# amp01.net
KiCad netlist of a schematic drawn in EAGLE
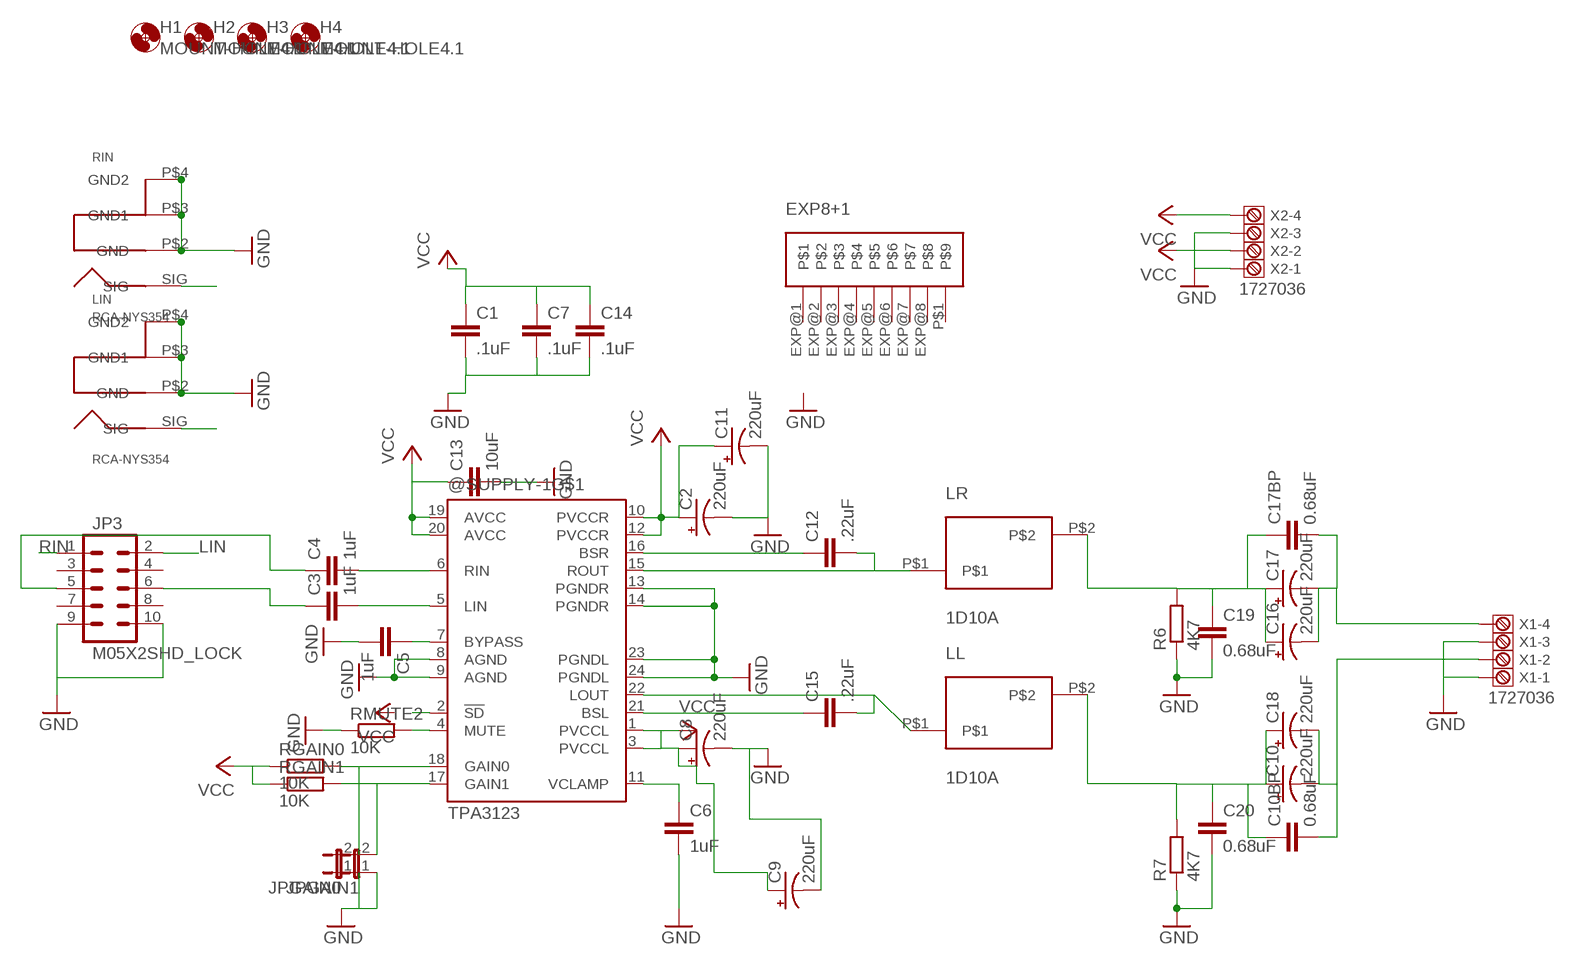
[diagram p0: schematic, sheet 1]

(export (version "E")
  (design (tool "Eeschema 10.0.6"))
  (components
    (comp (ref "@SUPPLY-1")
      (value "TPA3123")
      (footprint "eagle-import:PWP-TSSOP24")
      (libsource (lib "eagle-import") (part "TPA3123"))
    )
    (comp (ref "C1")
      (value ".1uF")
      (footprint "eagle-import:C0805")
      (libsource (lib "eagle-import") (part "C-EUC0805"))
    )
    (comp (ref "C2")
      (value "220uF")
      (footprint "eagle-import:PANASONIC_F")
      (libsource (lib "eagle-import") (part "CPOL-USF"))
    )
    (comp (ref "C3")
      (value "1uF")
      (footprint "eagle-import:C102_152-062X184")
      (libsource (lib "eagle-import") (part "C-EU102_152-062X184"))
    )
    (comp (ref "C4")
      (value "1uF")
      (footprint "eagle-import:C102_152-062X184")
      (libsource (lib "eagle-import") (part "C-EU102_152-062X184"))
    )
    (comp (ref "C5")
      (value "1uF")
      (footprint "eagle-import:C0805")
      (libsource (lib "eagle-import") (part "C-EUC0805"))
    )
    (comp (ref "C6")
      (value "1uF")
      (footprint "eagle-import:C0805")
      (libsource (lib "eagle-import") (part "C-EUC0805"))
    )
    (comp (ref "C7")
      (value ".1uF")
      (footprint "eagle-import:C0805")
      (libsource (lib "eagle-import") (part "C-EUC0805"))
    )
    (comp (ref "C8")
      (value "220uF")
      (footprint "eagle-import:PANASONIC_F")
      (libsource (lib "eagle-import") (part "CPOL-USF"))
    )
    (comp (ref "C9")
      (value "220uF")
      (footprint "eagle-import:PANASONIC_F")
      (libsource (lib "eagle-import") (part "CPOL-USF"))
    )
    (comp (ref "C10")
      (value "220uF")
      (footprint "eagle-import:PANASONIC_F")
      (libsource (lib "eagle-import") (part "CPOL-USF"))
    )
    (comp (ref "C10BP")
      (value "0.68uF")
      (footprint "eagle-import:C050-055X075")
      (libsource (lib "eagle-import") (part "C-EU050-055X075"))
    )
    (comp (ref "C11")
      (value "220uF")
      (footprint "eagle-import:PANASONIC_F")
      (libsource (lib "eagle-import") (part "CPOL-USF"))
    )
    (comp (ref "C12")
      (value ".22uF")
      (footprint "eagle-import:C0805")
      (libsource (lib "eagle-import") (part "C-EUC0805"))
    )
    (comp (ref "C13")
      (value "10uF")
      (footprint "eagle-import:C1210")
      (libsource (lib "eagle-import") (part "C-EUC1210"))
    )
    (comp (ref "C14")
      (value ".1uF")
      (footprint "eagle-import:C0805")
      (libsource (lib "eagle-import") (part "C-EUC0805"))
    )
    (comp (ref "C15")
      (value ".22uF")
      (footprint "eagle-import:C0805")
      (libsource (lib "eagle-import") (part "C-EUC0805"))
    )
    (comp (ref "C16")
      (value "220uF")
      (footprint "eagle-import:PANASONIC_F")
      (libsource (lib "eagle-import") (part "CPOL-USF"))
    )
    (comp (ref "C17")
      (value "220uF")
      (footprint "eagle-import:PANASONIC_F")
      (libsource (lib "eagle-import") (part "CPOL-USF"))
    )
    (comp (ref "C17BP")
      (value "0.68uF")
      (footprint "eagle-import:C050-055X075")
      (libsource (lib "eagle-import") (part "C-EU050-055X075"))
    )
    (comp (ref "C18")
      (value "220uF")
      (footprint "eagle-import:PANASONIC_F")
      (libsource (lib "eagle-import") (part "CPOL-USF"))
    )
    (comp (ref "C19")
      (value "0.68uF")
      (footprint "eagle-import:C050-055X075")
      (libsource (lib "eagle-import") (part "C-EU050-055X075"))
    )
    (comp (ref "C20")
      (value "0.68uF")
      (footprint "eagle-import:C050-055X075")
      (libsource (lib "eagle-import") (part "C-EU050-055X075"))
    )
    (comp (ref "H1")
      (value "MOUNT-HOLE4.1")
      (footprint "eagle-import:4,1")
      (libsource (lib "eagle-import") (part "MOUNT-HOLE4.1"))
    )
    (comp (ref "H2")
      (value "MOUNT-HOLE4.1")
      (footprint "eagle-import:4,1")
      (libsource (lib "eagle-import") (part "MOUNT-HOLE4.1"))
    )
    (comp (ref "H3")
      (value "MOUNT-HOLE4.1")
      (footprint "eagle-import:4,1")
      (libsource (lib "eagle-import") (part "MOUNT-HOLE4.1"))
    )
    (comp (ref "H4")
      (value "MOUNT-HOLE4.1")
      (footprint "eagle-import:4,1")
      (libsource (lib "eagle-import") (part "MOUNT-HOLE4.1"))
    )
    (comp (ref "JP3")
      (value "M05X2SHD_LOCK")
      (footprint "eagle-import:2X5-SHROUDED_LOCK")
      (libsource (lib "eagle-import") (part "M05X2SHD_LOCK"))
    )
    (comp (ref "JPGAIN0")
      (value "JUMPER-2PTH_LOCK")
      (footprint "eagle-import:1X02_LOCK")
      (libsource (lib "eagle-import") (part "JUMPER-2PTH_LOCK"))
    )
    (comp (ref "JPGAIN1")
      (value "JUMPER-2PTH_LOCK")
      (footprint "eagle-import:1X02_LOCK")
      (libsource (lib "eagle-import") (part "JUMPER-2PTH_LOCK"))
    )
    (comp (ref "LIN")
      (value "RCA-NYS354")
      (footprint "eagle-import:NYS354")
      (libsource (lib "eagle-import") (part "RCA-NYS354"))
    )
    (comp (ref "LL")
      (value "1D10A")
      (footprint "eagle-import:1D10APAC")
      (libsource (lib "eagle-import") (part "1D10A"))
    )
    (comp (ref "LR")
      (value "1D10A")
      (footprint "eagle-import:1D10APAC")
      (libsource (lib "eagle-import") (part "1D10A"))
    )
    (comp (ref "R6")
      (value "4K7")
      (footprint "eagle-import:R0805")
      (libsource (lib "eagle-import") (part "R-EU_R0805"))
    )
    (comp (ref "R7")
      (value "4K7")
      (footprint "eagle-import:R0805")
      (libsource (lib "eagle-import") (part "R-EU_R0805"))
    )
    (comp (ref "RGAIN0")
      (value "10K")
      (footprint "eagle-import:R0805")
      (libsource (lib "eagle-import") (part "R-EU_R0805"))
    )
    (comp (ref "RGAIN1")
      (value "10K")
      (footprint "eagle-import:R0805")
      (libsource (lib "eagle-import") (part "R-EU_R0805"))
    )
    (comp (ref "RIN")
      (value "RCA-NYS354")
      (footprint "eagle-import:NYS354")
      (libsource (lib "eagle-import") (part "RCA-NYS354"))
    )
    (comp (ref "RMUTE2")
      (value "10K")
      (footprint "eagle-import:R0805")
      (libsource (lib "eagle-import") (part "R-EU_R0805"))
    )
    (comp (ref "X1")
      (value "1727036")
      (footprint "eagle-import:1727036")
      (fields (field (name "MF") "FARNELL"))
      (libsource (lib "eagle-import") (part "1727036"))
    )
    (comp (ref "X2")
      (value "1727036")
      (footprint "eagle-import:1727036")
      (fields
        (field (name "MF") "FARNELL")
        (field (name "MF_1") "FARNELL")
        (field (name "MPN") "1727036")
        (field (name "OC_FARNELL") "3704592")
        (field (name "OC_NEWARK") "71C4114")
      )
      (libsource (lib "eagle-import") (part "1727036"))
    )
  )
  (nets
    (net (code "1") (name "/LIN") (class "Default")
      (node (ref "JP3") (pin "2") (pinfunction "2_2") (pintype "passive"))
      (node (ref "LIN") (pin "SIG") (pinfunction "SIG_SIG") (pintype "bidirectional"))
    )
    (net (code "2") (name "/RIN") (class "Default")
      (node (ref "JP3") (pin "1") (pinfunction "1_1") (pintype "passive"))
      (node (ref "RIN") (pin "SIG") (pinfunction "SIG_SIG") (pintype "bidirectional"))
    )
    (net (code "3") (name "GND") (class "Default")
      (node (ref "@SUPPLY-1") (pin "13") (pinfunction "PGNDR_13") (pintype "input"))
      (node (ref "@SUPPLY-1") (pin "14") (pinfunction "PGNDR_14") (pintype "input"))
      (node (ref "@SUPPLY-1") (pin "23") (pinfunction "PGNDL_23") (pintype "input"))
      (node (ref "@SUPPLY-1") (pin "24") (pinfunction "PGNDL_24") (pintype "input"))
      (node (ref "@SUPPLY-1") (pin "8") (pinfunction "AGND_8") (pintype "input"))
      (node (ref "@SUPPLY-1") (pin "9") (pinfunction "AGND_9") (pintype "input"))
      (node (ref "C1") (pin "2") (pinfunction "2_2") (pintype "passive"))
      (node (ref "C11") (pin "-") (pinfunction "-_-") (pintype "passive"))
      (node (ref "C13") (pin "2") (pinfunction "2_2") (pintype "passive"))
      (node (ref "C14") (pin "2") (pinfunction "2_2") (pintype "passive"))
      (node (ref "C19") (pin "2") (pinfunction "2_2") (pintype "passive"))
      (node (ref "C2") (pin "-") (pinfunction "-_-") (pintype "passive"))
      (node (ref "C20") (pin "2") (pinfunction "2_2") (pintype "passive"))
      (node (ref "C5") (pin "2") (pinfunction "2_2") (pintype "passive"))
      (node (ref "C6") (pin "2") (pinfunction "2_2") (pintype "passive"))
      (node (ref "C7") (pin "2") (pinfunction "2_2") (pintype "passive"))
      (node (ref "C8") (pin "-") (pinfunction "-_-") (pintype "passive"))
      (node (ref "C9") (pin "-") (pinfunction "-_-") (pintype "passive"))
      (node (ref "JP3") (pin "10") (pinfunction "10_10") (pintype "passive"))
      (node (ref "JP3") (pin "9") (pinfunction "9_9") (pintype "passive"))
      (node (ref "JPGAIN0") (pin "1") (pinfunction "1_1") (pintype "passive"))
      (node (ref "JPGAIN1") (pin "1") (pinfunction "1_1") (pintype "passive"))
      (node (ref "LIN") (pin "P$2") (pinfunction "GND_P$2") (pintype "bidirectional"))
      (node (ref "LIN") (pin "P$3") (pinfunction "GND1_P$3") (pintype "bidirectional"))
      (node (ref "LIN") (pin "P$4") (pinfunction "GND2_P$4") (pintype "bidirectional"))
      (node (ref "R6") (pin "1") (pinfunction "1_1") (pintype "passive"))
      (node (ref "R7") (pin "1") (pinfunction "1_1") (pintype "passive"))
      (node (ref "RIN") (pin "P$2") (pinfunction "GND_P$2") (pintype "bidirectional"))
      (node (ref "RIN") (pin "P$3") (pinfunction "GND1_P$3") (pintype "bidirectional"))
      (node (ref "RIN") (pin "P$4") (pinfunction "GND2_P$4") (pintype "bidirectional"))
      (node (ref "RMUTE2") (pin "1") (pinfunction "1_1") (pintype "passive"))
      (node (ref "X1") (pin "1") (pinfunction "1_1") (pintype "passive"))
      (node (ref "X1") (pin "3") (pinfunction "1_3") (pintype "passive"))
      (node (ref "X2") (pin "1") (pinfunction "1_1") (pintype "passive"))
      (node (ref "X2") (pin "3") (pinfunction "1_3") (pintype "passive"))
    )
    (net (code "4") (name "Net-(@SUPPLY-1A-BSL)") (class "Default")
      (node (ref "@SUPPLY-1") (pin "21") (pinfunction "BSL_21") (pintype "passive"))
      (node (ref "C15") (pin "1") (pinfunction "1_1") (pintype "passive"))
    )
    (net (code "5") (name "Net-(@SUPPLY-1A-BSR)") (class "Default")
      (node (ref "@SUPPLY-1") (pin "16") (pinfunction "BSR_16") (pintype "passive"))
      (node (ref "C12") (pin "1") (pinfunction "1_1") (pintype "passive"))
    )
    (net (code "6") (name "Net-(@SUPPLY-1A-BYPASS)") (class "Default")
      (node (ref "@SUPPLY-1") (pin "7") (pinfunction "BYPASS_7") (pintype "input"))
      (node (ref "C5") (pin "1") (pinfunction "1_1") (pintype "passive"))
    )
    (net (code "7") (name "Net-(@SUPPLY-1A-GAIN0)") (class "Default")
      (node (ref "@SUPPLY-1") (pin "18") (pinfunction "GAIN0_18") (pintype "input"))
      (node (ref "JPGAIN0") (pin "2") (pinfunction "2_2") (pintype "passive"))
      (node (ref "RGAIN0") (pin "2") (pinfunction "2_2") (pintype "passive"))
    )
    (net (code "8") (name "Net-(@SUPPLY-1A-GAIN1)") (class "Default")
      (node (ref "@SUPPLY-1") (pin "17") (pinfunction "GAIN1_17") (pintype "input"))
      (node (ref "JPGAIN1") (pin "2") (pinfunction "2_2") (pintype "passive"))
      (node (ref "RGAIN1") (pin "2") (pinfunction "2_2") (pintype "passive"))
    )
    (net (code "9") (name "Net-(@SUPPLY-1A-LIN)") (class "Default")
      (node (ref "@SUPPLY-1") (pin "5") (pinfunction "LIN_5") (pintype "input"))
      (node (ref "C3") (pin "2") (pinfunction "2_2") (pintype "passive"))
    )
    (net (code "10") (name "Net-(@SUPPLY-1A-LOUT)") (class "Default")
      (node (ref "@SUPPLY-1") (pin "22") (pinfunction "LOUT_22") (pintype "output"))
      (node (ref "C15") (pin "2") (pinfunction "2_2") (pintype "passive"))
      (node (ref "LL") (pin "P$1") (pinfunction "P$1_P$1") (pintype "bidirectional"))
    )
    (net (code "11") (name "Net-(@SUPPLY-1A-MUTE)") (class "Default")
      (node (ref "@SUPPLY-1") (pin "4") (pinfunction "MUTE_4") (pintype "input"))
      (node (ref "RMUTE2") (pin "2") (pinfunction "2_2") (pintype "passive"))
    )
    (net (code "12") (name "Net-(@SUPPLY-1A-RIN)") (class "Default")
      (node (ref "@SUPPLY-1") (pin "6") (pinfunction "RIN_6") (pintype "input"))
      (node (ref "C4") (pin "2") (pinfunction "2_2") (pintype "passive"))
    )
    (net (code "13") (name "Net-(@SUPPLY-1A-ROUT)") (class "Default")
      (node (ref "@SUPPLY-1") (pin "15") (pinfunction "ROUT_15") (pintype "output"))
      (node (ref "C12") (pin "2") (pinfunction "2_2") (pintype "passive"))
      (node (ref "LR") (pin "P$1") (pinfunction "P$1_P$1") (pintype "bidirectional"))
    )
    (net (code "14") (name "Net-(@SUPPLY-1A-VCLAMP)") (class "Default")
      (node (ref "@SUPPLY-1") (pin "11") (pinfunction "VCLAMP_11") (pintype "input"))
      (node (ref "C6") (pin "1") (pinfunction "1_1") (pintype "passive"))
    )
    (net (code "15") (name "Net-(C3-Pad1)") (class "Default")
      (node (ref "C3") (pin "1") (pinfunction "1_1") (pintype "passive"))
      (node (ref "JP3") (pin "6") (pinfunction "6_6") (pintype "passive"))
    )
    (net (code "16") (name "Net-(C4-Pad1)") (class "Default")
      (node (ref "C4") (pin "1") (pinfunction "1_1") (pintype "passive"))
      (node (ref "JP3") (pin "5") (pinfunction "5_5") (pintype "passive"))
    )
    (net (code "17") (name "Net-(C10-Pad+)") (class "Default")
      (node (ref "C10") (pin "+") (pinfunction "+_+") (pintype "passive"))
      (node (ref "C10BP") (pin "1") (pinfunction "1_1") (pintype "passive"))
      (node (ref "C18") (pin "+") (pinfunction "+_+") (pintype "passive"))
      (node (ref "C20") (pin "1") (pinfunction "1_1") (pintype "passive"))
      (node (ref "LL") (pin "P$2") (pinfunction "P$2_P$2") (pintype "bidirectional"))
      (node (ref "R7") (pin "2") (pinfunction "2_2") (pintype "passive"))
    )
    (net (code "18") (name "Net-(C16-Pad+)") (class "Default")
      (node (ref "C16") (pin "+") (pinfunction "+_+") (pintype "passive"))
      (node (ref "C17") (pin "+") (pinfunction "+_+") (pintype "passive"))
      (node (ref "C17BP") (pin "1") (pinfunction "1_1") (pintype "passive"))
      (node (ref "C19") (pin "1") (pinfunction "1_1") (pintype "passive"))
      (node (ref "LR") (pin "P$2") (pinfunction "P$2_P$2") (pintype "bidirectional"))
      (node (ref "R6") (pin "2") (pinfunction "2_2") (pintype "passive"))
    )
    (net (code "19") (name "Net-(X1B-1)") (class "Default")
      (node (ref "C10") (pin "-") (pinfunction "-_-") (pintype "passive"))
      (node (ref "C10BP") (pin "2") (pinfunction "2_2") (pintype "passive"))
      (node (ref "C18") (pin "-") (pinfunction "-_-") (pintype "passive"))
      (node (ref "X1") (pin "2") (pinfunction "1_2") (pintype "passive"))
    )
    (net (code "20") (name "Net-(X1D-1)") (class "Default")
      (node (ref "C16") (pin "-") (pinfunction "-_-") (pintype "passive"))
      (node (ref "C17") (pin "-") (pinfunction "-_-") (pintype "passive"))
      (node (ref "C17BP") (pin "2") (pinfunction "2_2") (pintype "passive"))
      (node (ref "X1") (pin "4") (pinfunction "1_4") (pintype "passive"))
    )
    (net (code "21") (name "VCC") (class "Default")
      (node (ref "@SUPPLY-1") (pin "1") (pinfunction "PVCCL_1") (pintype "input"))
      (node (ref "@SUPPLY-1") (pin "10") (pinfunction "PVCCR_10") (pintype "input"))
      (node (ref "@SUPPLY-1") (pin "12") (pinfunction "PVCCR_12") (pintype "input"))
      (node (ref "@SUPPLY-1") (pin "19") (pinfunction "AVCC_19") (pintype "input"))
      (node (ref "@SUPPLY-1") (pin "20") (pinfunction "AVCC_20") (pintype "input"))
      (node (ref "@SUPPLY-1") (pin "3") (pinfunction "PVCCL_3") (pintype "input"))
      (node (ref "C1") (pin "1") (pinfunction "1_1") (pintype "passive"))
      (node (ref "C11") (pin "+") (pinfunction "+_+") (pintype "passive"))
      (node (ref "C13") (pin "1") (pinfunction "1_1") (pintype "passive"))
      (node (ref "C14") (pin "1") (pinfunction "1_1") (pintype "passive"))
      (node (ref "C2") (pin "+") (pinfunction "+_+") (pintype "passive"))
      (node (ref "C7") (pin "1") (pinfunction "1_1") (pintype "passive"))
      (node (ref "C8") (pin "+") (pinfunction "+_+") (pintype "passive"))
      (node (ref "C9") (pin "+") (pinfunction "+_+") (pintype "passive"))
      (node (ref "RGAIN0") (pin "1") (pinfunction "1_1") (pintype "passive"))
      (node (ref "RGAIN1") (pin "1") (pinfunction "1_1") (pintype "passive"))
      (node (ref "X2") (pin "2") (pinfunction "1_2") (pintype "passive"))
      (node (ref "X2") (pin "4") (pinfunction "1_4") (pintype "passive"))
    )
    (net (code "22") (name "unconnected-(@SUPPLY-1A-~{SD}-Pad2)") (class "Default")
      (node (ref "@SUPPLY-1") (pin "2") (pinfunction "~{SD}_2") (pintype "input"))
    )
    (net (code "23") (name "unconnected-(@SUPPLY-1B-P$1-PadEXP@1)") (class "Default")
      (node (ref "@SUPPLY-1") (pin "EXP@1") (pinfunction "P$1_EXP@1") (pintype "bidirectional"))
    )
    (net (code "24") (name "unconnected-(@SUPPLY-1B-P$2-PadEXP@2)") (class "Default")
      (node (ref "@SUPPLY-1") (pin "EXP@2") (pinfunction "P$2_EXP@2") (pintype "bidirectional"))
    )
    (net (code "25") (name "unconnected-(@SUPPLY-1B-P$3-PadEXP@3)") (class "Default")
      (node (ref "@SUPPLY-1") (pin "EXP@3") (pinfunction "P$3_EXP@3") (pintype "bidirectional"))
    )
    (net (code "26") (name "unconnected-(@SUPPLY-1B-P$4-PadEXP@4)") (class "Default")
      (node (ref "@SUPPLY-1") (pin "EXP@4") (pinfunction "P$4_EXP@4") (pintype "bidirectional"))
    )
    (net (code "27") (name "unconnected-(@SUPPLY-1B-P$5-PadEXP@5)") (class "Default")
      (node (ref "@SUPPLY-1") (pin "EXP@5") (pinfunction "P$5_EXP@5") (pintype "bidirectional"))
    )
    (net (code "28") (name "unconnected-(@SUPPLY-1B-P$6-PadEXP@6)") (class "Default")
      (node (ref "@SUPPLY-1") (pin "EXP@6") (pinfunction "P$6_EXP@6") (pintype "bidirectional"))
    )
    (net (code "29") (name "unconnected-(@SUPPLY-1B-P$7-PadEXP@7)") (class "Default")
      (node (ref "@SUPPLY-1") (pin "EXP@7") (pinfunction "P$7_EXP@7") (pintype "bidirectional"))
    )
    (net (code "30") (name "unconnected-(@SUPPLY-1B-P$8-PadEXP@8)") (class "Default")
      (node (ref "@SUPPLY-1") (pin "EXP@8") (pinfunction "P$8_EXP@8") (pintype "bidirectional"))
    )
    (net (code "31") (name "unconnected-(@SUPPLY-1B-P$9-PadP$1)") (class "Default")
      (node (ref "@SUPPLY-1") (pin "P$1") (pinfunction "P$9_P$1") (pintype "bidirectional"))
    )
    (net (code "32") (name "unconnected-(JP3-Pad3)") (class "Default")
      (node (ref "JP3") (pin "3") (pinfunction "3_3") (pintype "passive"))
    )
    (net (code "33") (name "unconnected-(JP3-Pad4)") (class "Default")
      (node (ref "JP3") (pin "4") (pinfunction "4_4") (pintype "passive"))
    )
    (net (code "34") (name "unconnected-(JP3-Pad7)") (class "Default")
      (node (ref "JP3") (pin "7") (pinfunction "7_7") (pintype "passive"))
    )
    (net (code "35") (name "unconnected-(JP3-Pad8)") (class "Default")
      (node (ref "JP3") (pin "8") (pinfunction "8_8") (pintype "passive"))
    )
  )
)
